# Peripherals.net
KiCad netlist of a schematic drawn in Altium Designer
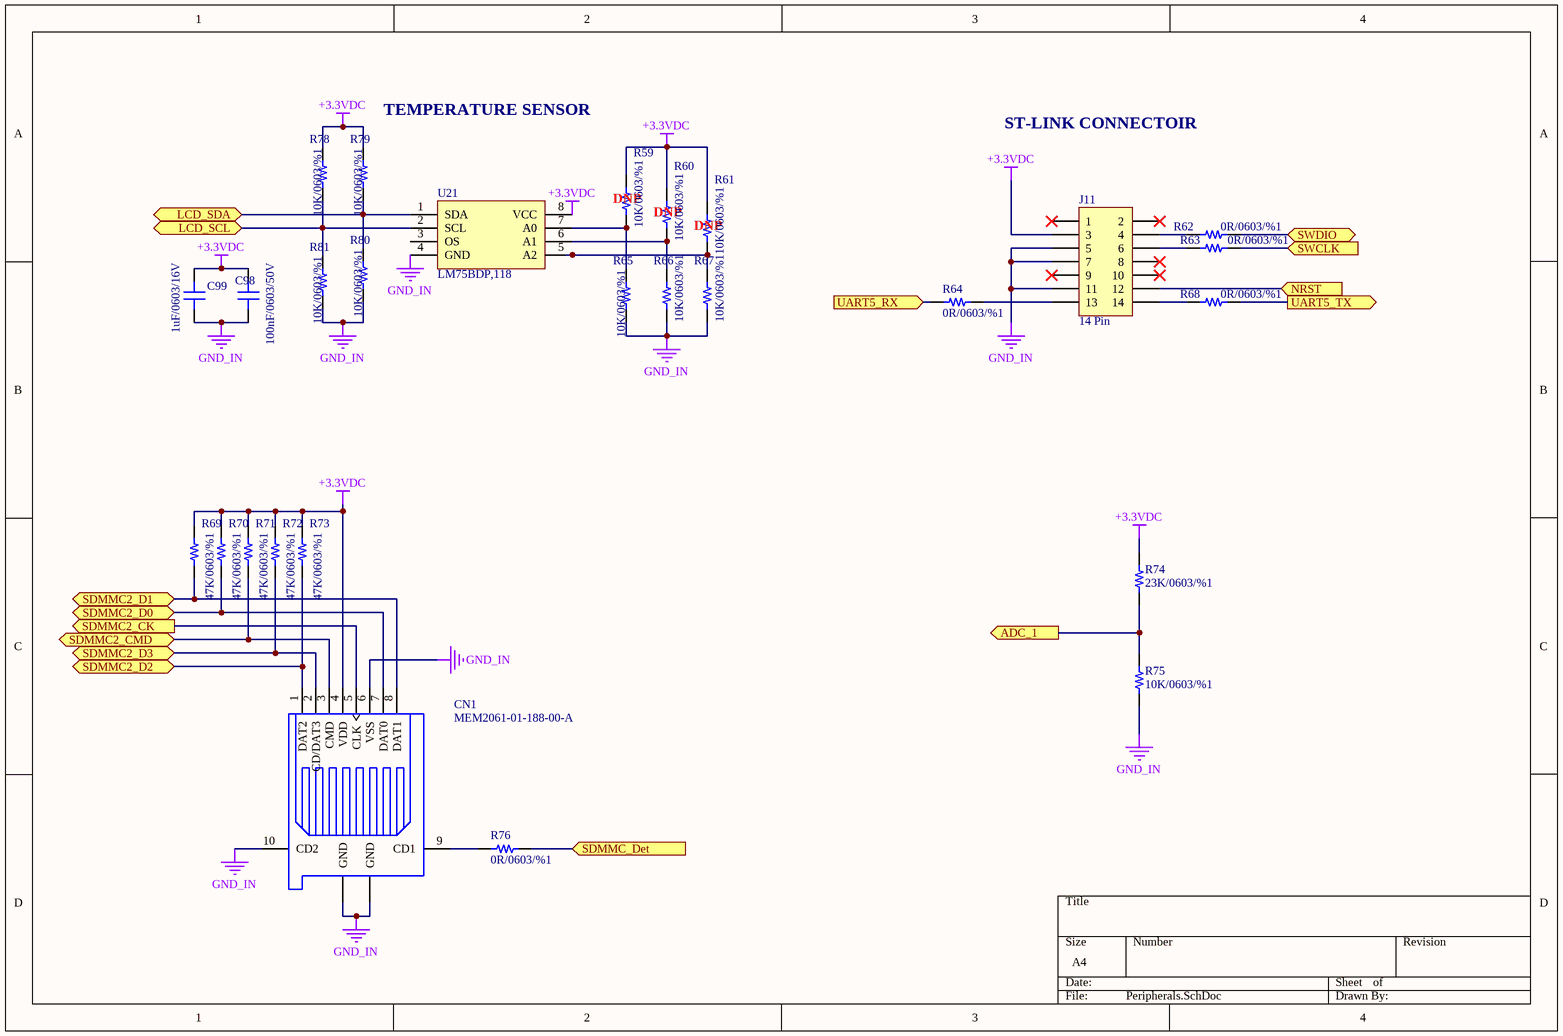
[diagram p0: Peripherals.SchDoc]

(export (version "E")
  (design (tool "Eeschema 10.0.6"))
  (components
    (comp (ref "C98")
      (value "100nF/0603/50V")
      (footprint "0603_cap")
      (libsource (lib "IM_v1.0") (part "Capacitor"))
    )
    (comp (ref "C99")
      (value "1uF/0603/16V")
      (footprint "0603_cap")
      (libsource (lib "IM_v1.0") (part "Capacitor"))
    )
    (comp (ref "CN1")
      (value "MEM2061-01-188-00-A")
      (footprint "GCT_MEM2061-01-188-00-A_REVA")
      (description "10 (8 + 2) Position Card Connector Secure Digital - microSD™ Surface Mount, Right Angle Gold")
      (libsource (lib "IM_v1.0") (part "MEM2061-01-188-00-A"))
    )
    (comp (ref "J11")
      (value "14 Pin")
      (footprint "L-KLS1-202C-14-S-B")
      (libsource (lib "IM_v1.0") (part "14 Pin"))
    )
    (comp (ref "R59")
      (value "10K/0603/%1")
      (footprint "0603_res")
      (fields (field (name "ASSEMBLY") "DNP"))
      (libsource (lib "IM_v1.0") (part "RES"))
    )
    (comp (ref "R60")
      (value "10K/0603/%1")
      (footprint "0603_res")
      (fields (field (name "ASSEMBLY") "DNP"))
      (libsource (lib "IM_v1.0") (part "RES"))
    )
    (comp (ref "R61")
      (value "10K/0603/%1")
      (footprint "0603_res")
      (fields (field (name "ASSEMBLY") "DNP"))
      (libsource (lib "IM_v1.0") (part "RES"))
    )
    (comp (ref "R62") (value "0R/0603/%1") (footprint "0603_res") (libsource (lib "IM_v1.0") (part "RES")))
    (comp (ref "R63") (value "0R/0603/%1") (footprint "0603_res") (libsource (lib "IM_v1.0") (part "RES")))
    (comp (ref "R64") (value "0R/0603/%1") (footprint "0603_res") (libsource (lib "IM_v1.0") (part "RES")))
    (comp (ref "R65") (value "10K/0603/%1") (footprint "0603_res") (libsource (lib "IM_v1.0") (part "RES")))
    (comp (ref "R66") (value "10K/0603/%1") (footprint "0603_res") (libsource (lib "IM_v1.0") (part "RES")))
    (comp (ref "R67") (value "10K/0603/%1") (footprint "0603_res") (libsource (lib "IM_v1.0") (part "RES")))
    (comp (ref "R68") (value "0R/0603/%1") (footprint "0603_res") (libsource (lib "IM_v1.0") (part "RES")))
    (comp (ref "R69") (value "47K/0603/%1") (footprint "0603_res") (libsource (lib "IM_v1.0") (part "RES")))
    (comp (ref "R70") (value "47K/0603/%1") (footprint "0603_res") (libsource (lib "IM_v1.0") (part "RES")))
    (comp (ref "R71") (value "47K/0603/%1") (footprint "0603_res") (libsource (lib "IM_v1.0") (part "RES")))
    (comp (ref "R72") (value "47K/0603/%1") (footprint "0603_res") (libsource (lib "IM_v1.0") (part "RES")))
    (comp (ref "R73") (value "47K/0603/%1") (footprint "0603_res") (libsource (lib "IM_v1.0") (part "RES")))
    (comp (ref "R74") (value "23K/0603/%1") (footprint "0603_res") (libsource (lib "IM_v1.0") (part "RES")))
    (comp (ref "R75") (value "10K/0603/%1") (footprint "0603_res") (libsource (lib "IM_v1.0") (part "RES")))
    (comp (ref "R76") (value "0R/0603/%1") (footprint "0603_res") (libsource (lib "IM_v1.0") (part "RES")))
    (comp (ref "R78") (value "10K/0603/%1") (footprint "0603_res") (libsource (lib "IM_v1.0") (part "RES")))
    (comp (ref "R79") (value "10K/0603/%1") (footprint "0603_res") (libsource (lib "IM_v1.0") (part "RES")))
    (comp (ref "R80") (value "10K/0603/%1") (footprint "0603_res") (libsource (lib "IM_v1.0") (part "RES")))
    (comp (ref "R81") (value "10K/0603/%1") (footprint "0603_res") (libsource (lib "IM_v1.0") (part "RES")))
    (comp (ref "U21")
      (value "LM75BDP,118")
      (footprint "8-tssop")
      (description "SENSOR DIGITAL -55C-125C 8TSSOP")
      (libsource (lib "IM_v1.0") (part "LM75BDP,118"))
    )
  )
  (nets
    (net (code "1") (name "+3.3VDC") (class "Default")
      (node (ref "C98") (pin "1") (pinfunction "1_1") (pintype "passive"))
      (node (ref "C99") (pin "2") (pinfunction "2_2") (pintype "passive"))
      (node (ref "CN1") (pin "4") (pinfunction "VDD_4") (pintype "passive"))
      (node (ref "J11") (pin "3") (pinfunction "3_3") (pintype "passive"))
      (node (ref "R59") (pin "1") (pinfunction "1_1") (pintype "passive"))
      (node (ref "R60") (pin "1") (pinfunction "1_1") (pintype "passive"))
      (node (ref "R61") (pin "1") (pinfunction "1_1") (pintype "passive"))
      (node (ref "R69") (pin "1") (pinfunction "1_1") (pintype "passive"))
      (node (ref "R70") (pin "1") (pinfunction "1_1") (pintype "passive"))
      (node (ref "R71") (pin "1") (pinfunction "1_1") (pintype "passive"))
      (node (ref "R72") (pin "1") (pinfunction "1_1") (pintype "passive"))
      (node (ref "R73") (pin "1") (pinfunction "1_1") (pintype "passive"))
      (node (ref "R74") (pin "1") (pinfunction "1_1") (pintype "passive"))
      (node (ref "R78") (pin "2") (pinfunction "2_2") (pintype "passive"))
      (node (ref "R79") (pin "2") (pinfunction "2_2") (pintype "passive"))
      (node (ref "U21") (pin "8") (pinfunction "VCC_8") (pintype "passive"))
    )
    (net (code "2") (name "/ADC_1") (class "Default")
      (node (ref "R74") (pin "2") (pinfunction "2_2") (pintype "passive"))
      (node (ref "R75") (pin "1") (pinfunction "1_1") (pintype "passive"))
    )
    (net (code "3") (name "/LCD_SCL") (class "Default")
      (node (ref "R78") (pin "1") (pinfunction "1_1") (pintype "passive"))
      (node (ref "R81") (pin "2") (pinfunction "2_2") (pintype "passive"))
      (node (ref "U21") (pin "2") (pinfunction "SCL_2") (pintype "passive"))
    )
    (net (code "4") (name "/LCD_SDA") (class "Default")
      (node (ref "R79") (pin "1") (pinfunction "1_1") (pintype "passive"))
      (node (ref "R80") (pin "2") (pinfunction "2_2") (pintype "passive"))
      (node (ref "U21") (pin "1") (pinfunction "SDA_1") (pintype "passive"))
    )
    (net (code "5") (name "/NRST") (class "Default")
      (node (ref "J11") (pin "12") (pinfunction "12_12") (pintype "passive"))
    )
    (net (code "6") (name "/SDMMC2_CK") (class "Default")
      (node (ref "CN1") (pin "5") (pinfunction "CLK_5") (pintype "passive"))
    )
    (net (code "7") (name "/SDMMC2_CMD") (class "Default")
      (node (ref "CN1") (pin "3") (pinfunction "CMD_3") (pintype "passive"))
      (node (ref "R71") (pin "2") (pinfunction "2_2") (pintype "passive"))
    )
    (net (code "8") (name "/SDMMC2_D0") (class "Default")
      (node (ref "CN1") (pin "7") (pinfunction "DAT0_7") (pintype "passive"))
      (node (ref "R70") (pin "2") (pinfunction "2_2") (pintype "passive"))
    )
    (net (code "9") (name "/SDMMC2_D1") (class "Default")
      (node (ref "CN1") (pin "8") (pinfunction "DAT1_8") (pintype "passive"))
      (node (ref "R69") (pin "2") (pinfunction "2_2") (pintype "passive"))
    )
    (net (code "10") (name "/SDMMC2_D2") (class "Default")
      (node (ref "CN1") (pin "1") (pinfunction "DAT2_1") (pintype "passive"))
      (node (ref "R73") (pin "2") (pinfunction "2_2") (pintype "passive"))
    )
    (net (code "11") (name "/SDMMC2_D3") (class "Default")
      (node (ref "CN1") (pin "2") (pinfunction "CD/DAT3_2") (pintype "passive"))
      (node (ref "R72") (pin "2") (pinfunction "2_2") (pintype "passive"))
    )
    (net (code "12") (name "/SDMMC_Det") (class "Default")
      (node (ref "R76") (pin "1") (pinfunction "1_1") (pintype "passive"))
    )
    (net (code "13") (name "/SWCLK") (class "Default")
      (node (ref "R63") (pin "1") (pinfunction "1_1") (pintype "passive"))
    )
    (net (code "14") (name "/SWDIO") (class "Default")
      (node (ref "R62") (pin "1") (pinfunction "1_1") (pintype "passive"))
    )
    (net (code "15") (name "/UART5_RX") (class "Default")
      (node (ref "R64") (pin "2") (pinfunction "2_2") (pintype "passive"))
    )
    (net (code "16") (name "/UART5_TX") (class "Default")
      (node (ref "R68") (pin "1") (pinfunction "1_1") (pintype "passive"))
    )
    (net (code "17") (name "GND_IN") (class "Default")
      (node (ref "C98") (pin "2") (pinfunction "2_2") (pintype "passive"))
      (node (ref "C99") (pin "1") (pinfunction "1_1") (pintype "passive"))
      (node (ref "CN1") (pin "10") (pinfunction "CD2_10") (pintype "passive"))
      (node (ref "CN1") (pin "11") (pinfunction "GND_11") (pintype "power_in"))
      (node (ref "CN1") (pin "12") (pinfunction "GND_12") (pintype "power_in"))
      (node (ref "CN1") (pin "6") (pinfunction "VSS_6") (pintype "passive"))
      (node (ref "J11") (pin "11") (pinfunction "11_11") (pintype "passive"))
      (node (ref "J11") (pin "5") (pinfunction "5_5") (pintype "passive"))
      (node (ref "J11") (pin "7") (pinfunction "7_7") (pintype "passive"))
      (node (ref "R65") (pin "1") (pinfunction "1_1") (pintype "passive"))
      (node (ref "R66") (pin "2") (pinfunction "2_2") (pintype "passive"))
      (node (ref "R67") (pin "2") (pinfunction "2_2") (pintype "passive"))
      (node (ref "R75") (pin "2") (pinfunction "2_2") (pintype "passive"))
      (node (ref "R80") (pin "1") (pinfunction "1_1") (pintype "passive"))
      (node (ref "R81") (pin "1") (pinfunction "1_1") (pintype "passive"))
      (node (ref "U21") (pin "4") (pinfunction "GND_4") (pintype "passive"))
    )
    (net (code "18") (name "Net-(CN1-CD1)") (class "Default")
      (node (ref "CN1") (pin "9") (pinfunction "CD1_9") (pintype "passive"))
      (node (ref "R76") (pin "2") (pinfunction "2_2") (pintype "passive"))
    )
    (net (code "19") (name "Net-(J11-Pad4)") (class "Default")
      (node (ref "J11") (pin "4") (pinfunction "4_4") (pintype "passive"))
      (node (ref "R62") (pin "2") (pinfunction "2_2") (pintype "passive"))
    )
    (net (code "20") (name "Net-(J11-Pad6)") (class "Default")
      (node (ref "J11") (pin "6") (pinfunction "6_6") (pintype "passive"))
      (node (ref "R63") (pin "2") (pinfunction "2_2") (pintype "passive"))
    )
    (net (code "21") (name "Net-(J11-Pad13)") (class "Default")
      (node (ref "J11") (pin "13") (pinfunction "13_13") (pintype "passive"))
      (node (ref "R64") (pin "1") (pinfunction "1_1") (pintype "passive"))
    )
    (net (code "22") (name "Net-(J11-Pad14)") (class "Default")
      (node (ref "J11") (pin "14") (pinfunction "14_14") (pintype "passive"))
      (node (ref "R68") (pin "2") (pinfunction "2_2") (pintype "passive"))
    )
    (net (code "23") (name "Net-(U21-A0)") (class "Default")
      (node (ref "R59") (pin "2") (pinfunction "2_2") (pintype "passive"))
      (node (ref "R65") (pin "2") (pinfunction "2_2") (pintype "passive"))
      (node (ref "U21") (pin "7") (pinfunction "A0_7") (pintype "passive"))
    )
    (net (code "24") (name "Net-(U21-A1)") (class "Default")
      (node (ref "R60") (pin "2") (pinfunction "2_2") (pintype "passive"))
      (node (ref "R66") (pin "1") (pinfunction "1_1") (pintype "passive"))
      (node (ref "U21") (pin "6") (pinfunction "A1_6") (pintype "passive"))
    )
    (net (code "25") (name "Net-(U21-A2)") (class "Default")
      (node (ref "R61") (pin "2") (pinfunction "2_2") (pintype "passive"))
      (node (ref "R67") (pin "1") (pinfunction "1_1") (pintype "passive"))
      (node (ref "U21") (pin "5") (pinfunction "A2_5") (pintype "passive"))
    )
    (net (code "26") (name "unconnected-(J11-Pad1)") (class "Default")
      (node (ref "J11") (pin "1") (pinfunction "1_1") (pintype "passive+no_connect"))
    )
    (net (code "27") (name "unconnected-(J11-Pad2)") (class "Default")
      (node (ref "J11") (pin "2") (pinfunction "2_2") (pintype "passive+no_connect"))
    )
    (net (code "28") (name "unconnected-(J11-Pad8)") (class "Default")
      (node (ref "J11") (pin "8") (pinfunction "8_8") (pintype "passive+no_connect"))
    )
    (net (code "29") (name "unconnected-(J11-Pad9)") (class "Default")
      (node (ref "J11") (pin "9") (pinfunction "9_9") (pintype "passive+no_connect"))
    )
    (net (code "30") (name "unconnected-(J11-Pad10)") (class "Default")
      (node (ref "J11") (pin "10") (pinfunction "10_10") (pintype "passive+no_connect"))
    )
    (net (code "31") (name "unconnected-(U21-OS-Pad3)") (class "Default")
      (node (ref "U21") (pin "3") (pinfunction "OS_3") (pintype "passive"))
    )
  )
)
